# 02_rf_front_end.net
KiCad netlist of a schematic drawn in Altium Designer
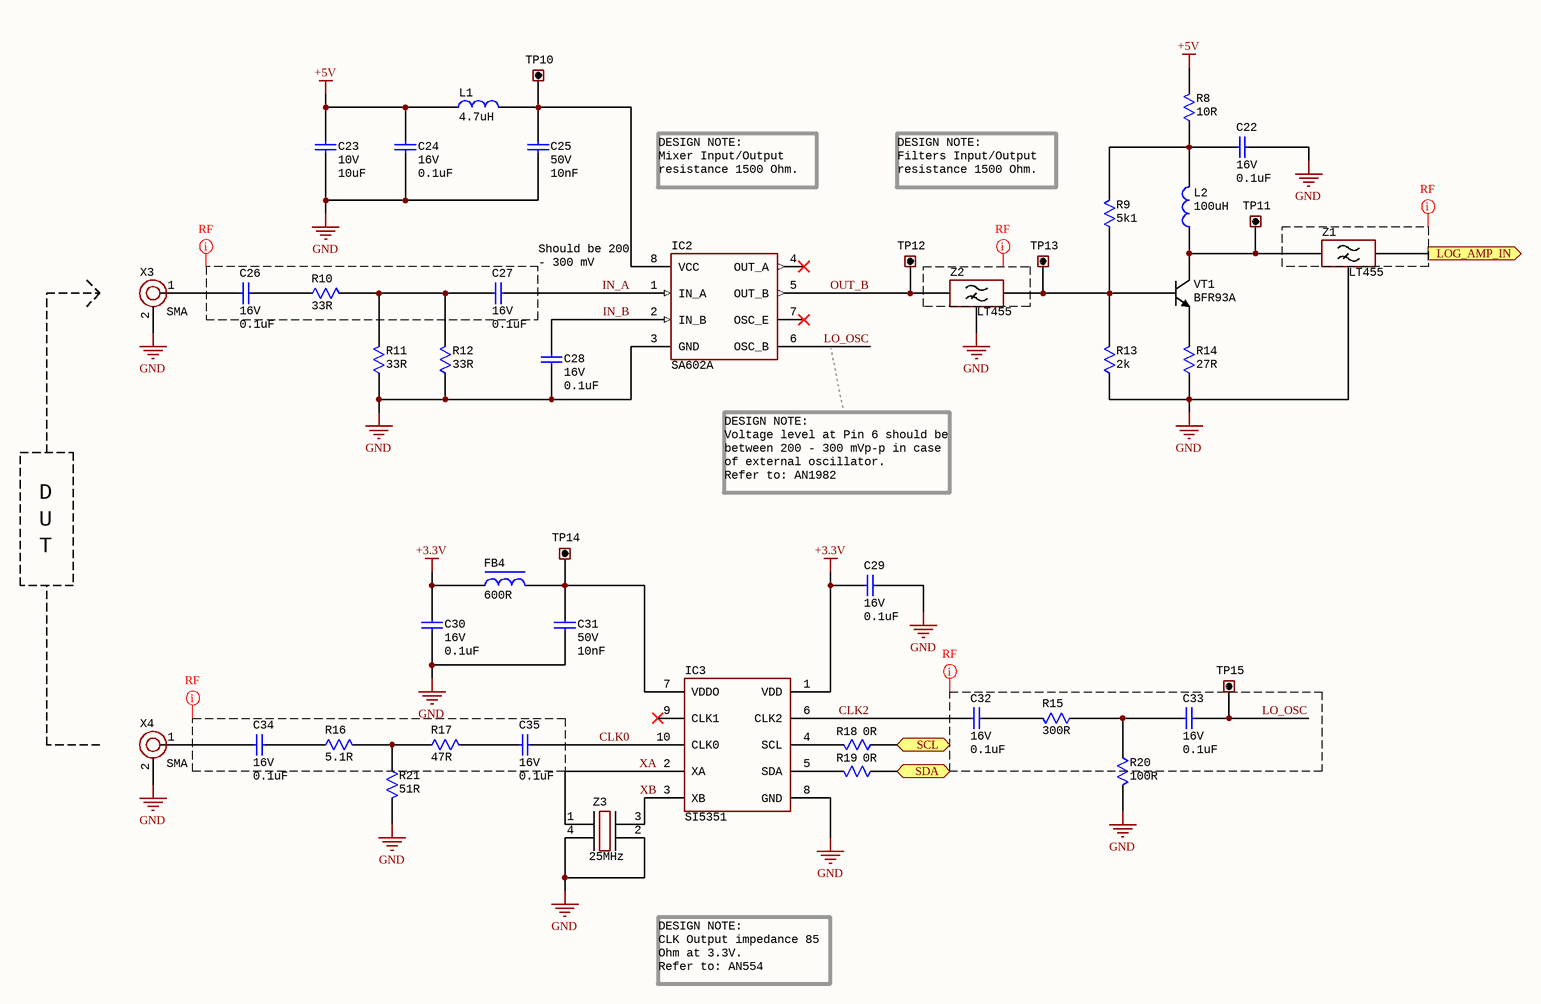
[diagram p0: 02_rf_front_end.SchDoc]

(export (version "E")
  (design (tool "Eeschema 10.0.6"))
  (components
    (comp (ref "C22")
      (value "0.1uF")
      (footprint "standard-case:CAP: 0402")
      (fields
        (field (name "MANUFACTURER") "Samsung Electro-Mechanics")
        (field (name "PARTNUMBER") "CL05B104KO5NNNC")
        (field (name "VALUEMANUFACTURERPARTNUMBER") "Ceramic capacitor, 0.1uF, X7R, ±10%, 16V, 0402, -55...+125°C")
        (field (name "VOLTAGE") "16V")
      )
      (libsource (lib "Schlib") (part "Ceramic"))
    )
    (comp (ref "C23")
      (value "10uF")
      (footprint "standard-case:CAP: 0603")
      (fields
        (field (name "MANUFACTURER") "Samsung Electro-Mechanics")
        (field (name "PARTNUMBER") "CL10A106KP8NNNC")
        (field (name "VALUEMANUFACTURERPARTNUMBER") "Ceramic capacitor, 10uF, X5R, ±10%, 10V, 0603, -55...+125°C")
        (field (name "VOLTAGE") "10V")
      )
      (libsource (lib "Schlib") (part "Ceramic"))
    )
    (comp (ref "C24")
      (value "0.1uF")
      (footprint "standard-case:CAP: 0402")
      (fields
        (field (name "MANUFACTURER") "Samsung Electro-Mechanics")
        (field (name "PARTNUMBER") "CL05B104KO5NNNC")
        (field (name "VALUEMANUFACTURERPARTNUMBER") "Ceramic capacitor, 0.1uF, X7R, ±10%, 16V, 0402, -55...+125°C")
        (field (name "VOLTAGE") "16V")
      )
      (libsource (lib "Schlib") (part "Ceramic"))
    )
    (comp (ref "C25")
      (value "10nF")
      (footprint "standard-case:CAP: 0402")
      (fields
        (field (name "MANUFACTURER") "Samsung Electro-Mechanics")
        (field (name "PARTNUMBER") "CL05B103KB5NNNC")
        (field (name "VALUEMANUFACTURERPARTNUMBER") "Ceramic capacitor, 10nF, X7R, ±10%, 50V, 0402, -55...+125°C")
        (field (name "VOLTAGE") "50V")
      )
      (libsource (lib "Schlib") (part "Ceramic"))
    )
    (comp (ref "C26")
      (value "0.1uF")
      (footprint "standard-case:CAP: 0402")
      (fields
        (field (name "MANUFACTURER") "Samsung Electro-Mechanics")
        (field (name "PARTNUMBER") "CL05B104KO5NNNC")
        (field (name "VALUEMANUFACTURERPARTNUMBER") "Ceramic capacitor, 0.1uF, X7R, ±10%, 16V, 0402, -55...+125°C")
        (field (name "VOLTAGE") "16V")
      )
      (libsource (lib "Schlib") (part "Ceramic"))
    )
    (comp (ref "C27")
      (value "0.1uF")
      (footprint "standard-case:CAP: 0402")
      (fields
        (field (name "MANUFACTURER") "Samsung Electro-Mechanics")
        (field (name "PARTNUMBER") "CL05B104KO5NNNC")
        (field (name "VALUEMANUFACTURERPARTNUMBER") "Ceramic capacitor, 0.1uF, X7R, ±10%, 16V, 0402, -55...+125°C")
        (field (name "VOLTAGE") "16V")
      )
      (libsource (lib "Schlib") (part "Ceramic"))
    )
    (comp (ref "C28")
      (value "0.1uF")
      (footprint "standard-case:CAP: 0402")
      (fields
        (field (name "MANUFACTURER") "Samsung Electro-Mechanics")
        (field (name "PARTNUMBER") "CL05B104KO5NNNC")
        (field (name "VALUEMANUFACTURERPARTNUMBER") "Ceramic capacitor, 0.1uF, X7R, ±10%, 16V, 0402, -55...+125°C")
        (field (name "VOLTAGE") "16V")
      )
      (libsource (lib "Schlib") (part "Ceramic"))
    )
    (comp (ref "C29")
      (value "0.1uF")
      (footprint "standard-case:CAP: 0402")
      (fields
        (field (name "MANUFACTURER") "Samsung Electro-Mechanics")
        (field (name "PARTNUMBER") "CL05B104KO5NNNC")
        (field (name "VALUEMANUFACTURERPARTNUMBER") "Ceramic capacitor, 0.1uF, X7R, ±10%, 16V, 0402, -55...+125°C")
        (field (name "VOLTAGE") "16V")
      )
      (libsource (lib "Schlib") (part "Ceramic"))
    )
    (comp (ref "C30")
      (value "0.1uF")
      (footprint "standard-case:CAP: 0402")
      (fields
        (field (name "MANUFACTURER") "Samsung Electro-Mechanics")
        (field (name "PARTNUMBER") "CL05B104KO5NNNC")
        (field (name "VALUEMANUFACTURERPARTNUMBER") "Ceramic capacitor, 0.1uF, X7R, ±10%, 16V, 0402, -55...+125°C")
        (field (name "VOLTAGE") "16V")
      )
      (libsource (lib "Schlib") (part "Ceramic"))
    )
    (comp (ref "C31")
      (value "10nF")
      (footprint "standard-case:CAP: 0402")
      (fields
        (field (name "MANUFACTURER") "Samsung Electro-Mechanics")
        (field (name "PARTNUMBER") "CL05B103KB5NNNC")
        (field (name "VALUEMANUFACTURERPARTNUMBER") "Ceramic capacitor, 10nF, X7R, ±10%, 50V, 0402, -55...+125°C")
        (field (name "VOLTAGE") "50V")
      )
      (libsource (lib "Schlib") (part "Ceramic"))
    )
    (comp (ref "C32")
      (value "0.1uF")
      (footprint "standard-case:CAP: 0402")
      (fields
        (field (name "MANUFACTURER") "Samsung Electro-Mechanics")
        (field (name "PARTNUMBER") "CL05B104KO5NNNC")
        (field (name "VALUEMANUFACTURERPARTNUMBER") "Ceramic capacitor, 0.1uF, X7R, ±10%, 16V, 0402, -55...+125°C")
        (field (name "VOLTAGE") "16V")
      )
      (libsource (lib "Schlib") (part "Ceramic"))
    )
    (comp (ref "C33")
      (value "0.1uF")
      (footprint "standard-case:CAP: 0402")
      (fields
        (field (name "MANUFACTURER") "Samsung Electro-Mechanics")
        (field (name "PARTNUMBER") "CL05B104KO5NNNC")
        (field (name "VALUEMANUFACTURERPARTNUMBER") "Ceramic capacitor, 0.1uF, X7R, ±10%, 16V, 0402, -55...+125°C")
        (field (name "VOLTAGE") "16V")
      )
      (libsource (lib "Schlib") (part "Ceramic"))
    )
    (comp (ref "C34")
      (value "0.1uF")
      (footprint "standard-case:CAP: 0402")
      (fields
        (field (name "MANUFACTURER") "Samsung Electro-Mechanics")
        (field (name "PARTNUMBER") "CL05B104KO5NNNC")
        (field (name "VALUEMANUFACTURERPARTNUMBER") "Ceramic capacitor, 0.1uF, X7R, ±10%, 16V, 0402, -55...+125°C")
        (field (name "VOLTAGE") "16V")
      )
      (libsource (lib "Schlib") (part "Ceramic"))
    )
    (comp (ref "C35")
      (value "0.1uF")
      (footprint "standard-case:CAP: 0402")
      (fields
        (field (name "MANUFACTURER") "Samsung Electro-Mechanics")
        (field (name "PARTNUMBER") "CL05B104KO5NNNC")
        (field (name "VALUEMANUFACTURERPARTNUMBER") "Ceramic capacitor, 0.1uF, X7R, ±10%, 16V, 0402, -55...+125°C")
        (field (name "VOLTAGE") "16V")
      )
      (libsource (lib "Schlib") (part "Ceramic"))
    )
    (comp (ref "FB4")
      (value "~")
      (footprint "standard-case:IND: 0603")
      (fields
        (field (name "MANUFACTURER") "Sunlord")
        (field (name "PARTNUMBER") "LQP03TNR10J02D")
        (field (name "VALUEMANUFACTURERPARTNUMBER") "Ferrite Bead, , , 0603, 200mA, -55...+125°C")
        (field (name "RESISTANCE") "600R")
      )
      (libsource (lib "Schlib") (part "Ferrite_Bead_SMD"))
    )
    (comp (ref "IC2")
      (value "SA602A")
      (footprint "8-SOIC")
      (description "Integrated Circuit")
      (fields
        (field (name "MANUFACTURER_PART_NUMBER") "SA602AD/01,118")
        (field (name "MOUSER PART NUMBER") "771-SA602AD/01-T")
      )
      (libsource (lib "Schlib") (part "SA602A"))
    )
    (comp (ref "IC3")
      (value "SI5351")
      (footprint "10-MSOP")
      (description "Integrated Circuit")
      (fields
        (field (name "MANUFACTURER_PART_NUMBER") "Si5351A-B-GT")
        (field (name "MOUSER PART NUMBER") "634-SI5351A-B-GT")
      )
      (libsource (lib "Schlib") (part "Si5351A"))
    )
    (comp (ref "L1")
      (value "4.7uH")
      (footprint "standard-case:IND: 0603")
      (fields
        (field (name "MANUFACTURER") "Murata Electronics")
        (field (name "PARTNUMBER") "LQP03TNR10J02D")
        (field (name "VALUEMANUFACTURERPARTNUMBER") "Fixed inductor, 4.7uH, ±5%, 0201, 80mA, -55...+125°C")
      )
      (libsource (lib "Schlib") (part "Inductor_SMD"))
    )
    (comp (ref "L2")
      (value "100uH")
      (footprint "standard-case:IND: 0805")
      (fields
        (field (name "MANUFACTURER") "Murata Electronics")
        (field (name "PARTNUMBER") "LQP03TNR10J02D")
        (field (name "VALUEMANUFACTURERPARTNUMBER") "Fixed inductor, 100uH, ±5%, 0201, 80mA, -55...+125°C")
      )
      (libsource (lib "Schlib") (part "Inductor_SMD"))
    )
    (comp (ref "R8")
      (value "10R")
      (footprint "standard-case:RES: 0603")
      (fields
        (field (name "MANUFACTURER") "Yageo")
        (field (name "PARTNUMBER") "RC0201JR-07100RL")
        (field (name "VALUEMANUFACTURERPARTNUMBER") "Resistor film, 10R, ±5%, 0603, 0.05W, -55...+125°C")
      )
      (libsource (lib "Schlib") (part "Resistor"))
    )
    (comp (ref "R9")
      (value "5k1")
      (footprint "standard-case:RES: 0603")
      (fields
        (field (name "MANUFACTURER") "Yageo")
        (field (name "PARTNUMBER") "RC0201JR-07100RL")
        (field (name "VALUEMANUFACTURERPARTNUMBER") "Resistor film, 5k1, ±5%, 0603, 0.05W, -55...+125°C")
      )
      (libsource (lib "Schlib") (part "Resistor"))
    )
    (comp (ref "R10")
      (value "33R")
      (footprint "standard-case:RES: 0603")
      (fields
        (field (name "MANUFACTURER") "Yageo")
        (field (name "PARTNUMBER") "RC0201JR-07100RL")
        (field (name "VALUEMANUFACTURERPARTNUMBER") "Resistor film, 33R, ±5%, 0603, 0.05W, -55...+125°C")
      )
      (libsource (lib "Schlib") (part "Resistor"))
    )
    (comp (ref "R11")
      (value "33R")
      (footprint "standard-case:RES: 0603")
      (fields
        (field (name "MANUFACTURER") "Yageo")
        (field (name "PARTNUMBER") "RC0201JR-07100RL")
        (field (name "VALUEMANUFACTURERPARTNUMBER") "Resistor film, 33R, ±5%, 0603, 0.05W, -55...+125°C")
      )
      (libsource (lib "Schlib") (part "Resistor"))
    )
    (comp (ref "R12")
      (value "33R")
      (footprint "standard-case:RES: 0603")
      (fields
        (field (name "MANUFACTURER") "Yageo")
        (field (name "PARTNUMBER") "RC0201JR-07100RL")
        (field (name "VALUEMANUFACTURERPARTNUMBER") "Resistor film, 33R, ±5%, 0603, 0.05W, -55...+125°C")
      )
      (libsource (lib "Schlib") (part "Resistor"))
    )
    (comp (ref "R13")
      (value "2k")
      (footprint "standard-case:RES: 0603")
      (fields
        (field (name "MANUFACTURER") "Yageo")
        (field (name "PARTNUMBER") "RC0201JR-07100RL")
        (field (name "VALUEMANUFACTURERPARTNUMBER") "Resistor film, 2k, ±5%, 0603, 0.05W, -55...+125°C")
      )
      (libsource (lib "Schlib") (part "Resistor"))
    )
    (comp (ref "R14")
      (value "27R")
      (footprint "standard-case:RES: 0603")
      (fields
        (field (name "MANUFACTURER") "Yageo")
        (field (name "PARTNUMBER") "RC0201JR-07100RL")
        (field (name "VALUEMANUFACTURERPARTNUMBER") "Resistor film, 27R, ±5%, 0603, 0.05W, -55...+125°C")
      )
      (libsource (lib "Schlib") (part "Resistor"))
    )
    (comp (ref "R15")
      (value "300R")
      (footprint "standard-case:RES: 0603")
      (fields
        (field (name "MANUFACTURER") "Yageo")
        (field (name "PARTNUMBER") "RC0201JR-07100RL")
        (field (name "VALUEMANUFACTURERPARTNUMBER") "Resistor film, 300R, ±5%, 0603, 0.05W, -55...+125°C")
      )
      (libsource (lib "Schlib") (part "Resistor"))
    )
    (comp (ref "R16")
      (value "5.1R")
      (footprint "standard-case:RES: 0603")
      (fields
        (field (name "MANUFACTURER") "Yageo")
        (field (name "PARTNUMBER") "RC0201JR-07100RL")
        (field (name "VALUEMANUFACTURERPARTNUMBER") "Resistor film, 5.1R, ±5%, 0603, 0.05W, -55...+125°C")
      )
      (libsource (lib "Schlib") (part "Resistor"))
    )
    (comp (ref "R17")
      (value "47R")
      (footprint "standard-case:RES: 0603")
      (fields
        (field (name "MANUFACTURER") "Yageo")
        (field (name "PARTNUMBER") "RC0201JR-07100RL")
        (field (name "VALUEMANUFACTURERPARTNUMBER") "Resistor film, 47R, ±5%, 0603, 0.05W, -55...+125°C")
      )
      (libsource (lib "Schlib") (part "Resistor"))
    )
    (comp (ref "R18")
      (value "0R")
      (footprint "standard-case:RES: 0402")
      (fields
        (field (name "MANUFACTURER") "Yageo")
        (field (name "PARTNUMBER") "RC0201JR-07100RL")
        (field (name "VALUEMANUFACTURERPARTNUMBER") "Resistor film, 0R, ±5%, 0603, 0.05W, -55...+125°C")
      )
      (libsource (lib "Schlib") (part "Resistor"))
    )
    (comp (ref "R19")
      (value "0R")
      (footprint "standard-case:RES: 0402")
      (fields
        (field (name "MANUFACTURER") "Yageo")
        (field (name "PARTNUMBER") "RC0201JR-07100RL")
        (field (name "VALUEMANUFACTURERPARTNUMBER") "Resistor film, 0R, ±5%, 0603, 0.05W, -55...+125°C")
      )
      (libsource (lib "Schlib") (part "Resistor"))
    )
    (comp (ref "R20")
      (value "100R")
      (footprint "standard-case:RES: 0603")
      (fields
        (field (name "MANUFACTURER") "Yageo")
        (field (name "PARTNUMBER") "RC0201JR-07100RL")
        (field (name "VALUEMANUFACTURERPARTNUMBER") "Resistor film, 100R, ±5%, 0603, 0.05W, -55...+125°C")
      )
      (libsource (lib "Schlib") (part "Resistor"))
    )
    (comp (ref "R21")
      (value "51R")
      (footprint "standard-case:RES: 0603")
      (fields
        (field (name "MANUFACTURER") "Yageo")
        (field (name "PARTNUMBER") "RC0201JR-07100RL")
        (field (name "VALUEMANUFACTURERPARTNUMBER") "Resistor film, 51R, ±5%, 0603, 0.05W, -55...+125°C")
      )
      (libsource (lib "Schlib") (part "Resistor"))
    )
    (comp (ref "TP10")
      (value "~")
      (footprint "CON: test_point")
      (fields
        (field (name "MANUFACTURER") "Keystone")
        (field (name "VALUEMANUFACTURERPARTNUMBER") "Test point, Keystone, 5001")
        (field (name "PARTNUMBER") "5001")
      )
      (libsource (lib "Schlib") (part "Connector_Test_Point"))
    )
    (comp (ref "TP11")
      (value "~")
      (footprint "CON: test_point")
      (fields
        (field (name "MANUFACTURER") "Keystone")
        (field (name "VALUEMANUFACTURERPARTNUMBER") "Test point, Keystone, 5001")
        (field (name "PARTNUMBER") "5001")
      )
      (libsource (lib "Schlib") (part "Connector_Test_Point"))
    )
    (comp (ref "TP12")
      (value "~")
      (footprint "CON: test_point")
      (fields
        (field (name "MANUFACTURER") "Keystone")
        (field (name "VALUEMANUFACTURERPARTNUMBER") "Test point, Keystone, 5001")
        (field (name "PARTNUMBER") "5001")
      )
      (libsource (lib "Schlib") (part "Connector_Test_Point"))
    )
    (comp (ref "TP13")
      (value "~")
      (footprint "CON: test_point")
      (fields
        (field (name "MANUFACTURER") "Keystone")
        (field (name "VALUEMANUFACTURERPARTNUMBER") "Test point, Keystone, 5001")
        (field (name "PARTNUMBER") "5001")
      )
      (libsource (lib "Schlib") (part "Connector_Test_Point"))
    )
    (comp (ref "TP14")
      (value "~")
      (footprint "CON: test_point")
      (fields
        (field (name "MANUFACTURER") "Keystone")
        (field (name "VALUEMANUFACTURERPARTNUMBER") "Test point, Keystone, 5001")
        (field (name "PARTNUMBER") "5001")
      )
      (libsource (lib "Schlib") (part "Connector_Test_Point"))
    )
    (comp (ref "TP15")
      (value "~")
      (footprint "CON: test_point")
      (fields
        (field (name "MANUFACTURER") "Keystone")
        (field (name "VALUEMANUFACTURERPARTNUMBER") "Test point, Keystone, 5001")
        (field (name "PARTNUMBER") "5001")
      )
      (libsource (lib "") (part "Connector_Test_Point_1"))
    )
    (comp (ref "VT1")
      (value "~")
      (footprint "standard-case:SOT23")
      (fields
        (field (name "MANUFACTURER") "ON Semiconductor")
        (field (name "VALUEMANUFACTURERPARTNUMBER") "NPN transistor, 45V, 100mA, 100MHz, 300mW, 0.6V, 420, SOT-23, -55...+125°C")
        (field (name "PARTNUMBER") "BFR93A")
      )
      (libsource (lib "Schlib") (part "BJT_NPN_132"))
    )
    (comp (ref "X3")
      (value "~")
      (footprint "CON: SMA EDGE MOUNT")
      (fields
        (field (name "MANUFACTURER") "TE Connectivity")
        (field (name "VALUEMANUFACTURERPARTNUMBER") "Connector SMA, 50 Ohm, 3GHz")
        (field (name "PARTNUMBER") "5-1814832-1")
        (field (name "COMMENTTEXT") "SMA")
      )
      (libsource (lib "Schlib") (part "Connector_SMA"))
    )
    (comp (ref "X4")
      (value "~")
      (footprint "CON: SMA EDGE MOUNT")
      (fields
        (field (name "MANUFACTURER") "TE Connectivity")
        (field (name "VALUEMANUFACTURERPARTNUMBER") "Connector SMA, 50 Ohm, 3GHz")
        (field (name "PARTNUMBER") "5-1814832-1")
        (field (name "COMMENTTEXT") "SMA")
      )
      (libsource (lib "Schlib") (part "Connector_SMA"))
    )
    (comp (ref "Z1")
      (value "~")
      (footprint "CFUKG455")
      (fields (field (name "PARTNUMBER") "LT455"))
      (libsource (lib "Schlib") (part "LT455"))
    )
    (comp (ref "Z2")
      (value "~")
      (footprint "CFUKG455")
      (fields (field (name "PARTNUMBER") "LT455"))
      (libsource (lib "Schlib") (part "LT455"))
    )
    (comp (ref "Z3")
      (value "~")
      (footprint "custom-case:OSC: 3225")
      (fields
        (field (name "MANUFACTURER") "Yangxing Tech")
        (field (name "PARTNUMBER") "X322525MOB4SI")
        (field (name "VALUEMANUFACTURERPARTNUMBER") "Oscilator, 25MHz, HCMOS, ±50ppm, case 3225, -20...+70°C")
        (field (name "FREQUENCY") "25MHz")
      )
      (libsource (lib "Schlib") (part "Oscilator"))
    )
  )
  (nets
    (net (code "1") (name "+3.3V") (class "Default")
      (node (ref "C29") (pin "1") (pinfunction "1_1") (pintype "passive"))
      (node (ref "C30") (pin "1") (pinfunction "1_1") (pintype "passive"))
      (node (ref "FB4") (pin "2") (pinfunction "2_2") (pintype "passive"))
      (node (ref "IC3") (pin "1") (pinfunction "VDD_1") (pintype "passive"))
    )
    (net (code "2") (name "+5V") (class "Default")
      (node (ref "C23") (pin "1") (pinfunction "1_1") (pintype "passive"))
      (node (ref "C24") (pin "1") (pinfunction "1_1") (pintype "passive"))
      (node (ref "L1") (pin "2") (pinfunction "2_2") (pintype "passive"))
      (node (ref "R8") (pin "2") (pinfunction "2_2") (pintype "passive"))
    )
    (net (code "3") (name "/CLK0") (class "Default")
      (node (ref "C35") (pin "1") (pinfunction "1_1") (pintype "passive"))
      (node (ref "IC3") (pin "10") (pinfunction "CLK0_10") (pintype "passive"))
    )
    (net (code "4") (name "/CLK2") (class "Default")
      (node (ref "C32") (pin "2") (pinfunction "2_2") (pintype "passive"))
      (node (ref "IC3") (pin "6") (pinfunction "CLK2_6") (pintype "passive"))
    )
    (net (code "5") (name "/IN_A") (class "Default")
      (node (ref "C27") (pin "2") (pinfunction "2_2") (pintype "passive"))
      (node (ref "IC2") (pin "1") (pinfunction "IN_A_1") (pintype "input"))
    )
    (net (code "6") (name "/IN_B") (class "Default")
      (node (ref "C28") (pin "2") (pinfunction "2_2") (pintype "passive"))
      (node (ref "IC2") (pin "2") (pinfunction "IN_B_2") (pintype "input"))
    )
    (net (code "7") (name "/LOG_AMP_IN") (class "Default")
      (node (ref "Z1") (pin "2") (pinfunction "OUT_2") (pintype "passive"))
    )
    (net (code "8") (name "/LO_OSC") (class "Default")
      (node (ref "C33") (pin "1") (pinfunction "1_1") (pintype "passive"))
      (node (ref "IC2") (pin "6") (pinfunction "OSC_B_6") (pintype "passive"))
      (node (ref "TP15") (pin "1") (pinfunction "1_1") (pintype "passive"))
    )
    (net (code "9") (name "/OUT_B") (class "Default")
      (node (ref "IC2") (pin "5") (pinfunction "OUT_B_5") (pintype "output"))
      (node (ref "TP12") (pin "1") (pinfunction "1_1") (pintype "passive"))
      (node (ref "Z2") (pin "1") (pinfunction "IN_1") (pintype "passive"))
    )
    (net (code "10") (name "/SCL") (class "Default")
      (node (ref "R18") (pin "1") (pinfunction "1_1") (pintype "passive"))
    )
    (net (code "11") (name "/SDA") (class "Default")
      (node (ref "R19") (pin "1") (pinfunction "1_1") (pintype "passive"))
    )
    (net (code "12") (name "/XA") (class "Default")
      (node (ref "IC3") (pin "2") (pinfunction "XA_2") (pintype "passive"))
      (node (ref "Z3") (pin "1") (pinfunction "1_1") (pintype "passive"))
    )
    (net (code "13") (name "/XB") (class "Default")
      (node (ref "IC3") (pin "3") (pinfunction "XB_3") (pintype "passive"))
      (node (ref "Z3") (pin "3") (pinfunction "3_3") (pintype "passive"))
    )
    (net (code "14") (name "GND") (class "Default")
      (node (ref "C22") (pin "2") (pinfunction "2_2") (pintype "passive"))
      (node (ref "C23") (pin "2") (pinfunction "2_2") (pintype "passive"))
      (node (ref "C24") (pin "2") (pinfunction "2_2") (pintype "passive"))
      (node (ref "C25") (pin "2") (pinfunction "2_2") (pintype "passive"))
      (node (ref "C28") (pin "1") (pinfunction "1_1") (pintype "passive"))
      (node (ref "C29") (pin "2") (pinfunction "2_2") (pintype "passive"))
      (node (ref "C30") (pin "2") (pinfunction "2_2") (pintype "passive"))
      (node (ref "C31") (pin "2") (pinfunction "2_2") (pintype "passive"))
      (node (ref "IC2") (pin "3") (pinfunction "GND_3") (pintype "power_in"))
      (node (ref "IC3") (pin "8") (pinfunction "GND_8") (pintype "passive"))
      (node (ref "R11") (pin "1") (pinfunction "1_1") (pintype "passive"))
      (node (ref "R12") (pin "1") (pinfunction "1_1") (pintype "passive"))
      (node (ref "R13") (pin "1") (pinfunction "1_1") (pintype "passive"))
      (node (ref "R14") (pin "1") (pinfunction "1_1") (pintype "passive"))
      (node (ref "R20") (pin "1") (pinfunction "1_1") (pintype "passive"))
      (node (ref "R21") (pin "1") (pinfunction "1_1") (pintype "passive"))
      (node (ref "X3") (pin "2") (pinfunction "2_2") (pintype "passive"))
      (node (ref "X4") (pin "2") (pinfunction "2_2") (pintype "passive"))
      (node (ref "Z1") (pin "3") (pinfunction "GND_3") (pintype "passive"))
      (node (ref "Z2") (pin "3") (pinfunction "GND_3") (pintype "passive"))
      (node (ref "Z3") (pin "2") (pinfunction "2_2") (pintype "passive"))
      (node (ref "Z3") (pin "4") (pinfunction "4_4") (pintype "passive"))
    )
    (net (code "15") (name "Net-(C22-Pad1)") (class "Default")
      (node (ref "C22") (pin "1") (pinfunction "1_1") (pintype "passive"))
      (node (ref "L2") (pin "1") (pinfunction "1_1") (pintype "passive"))
      (node (ref "R8") (pin "1") (pinfunction "1_1") (pintype "passive"))
      (node (ref "R9") (pin "2") (pinfunction "2_2") (pintype "passive"))
    )
    (net (code "16") (name "Net-(C26-Pad1)") (class "Default")
      (node (ref "C26") (pin "1") (pinfunction "1_1") (pintype "passive"))
      (node (ref "X3") (pin "1") (pinfunction "1_1") (pintype "passive"))
    )
    (net (code "17") (name "Net-(C26-Pad2)") (class "Default")
      (node (ref "C26") (pin "2") (pinfunction "2_2") (pintype "passive"))
      (node (ref "R10") (pin "1") (pinfunction "1_1") (pintype "passive"))
    )
    (net (code "18") (name "Net-(C27-Pad1)") (class "Default")
      (node (ref "C27") (pin "1") (pinfunction "1_1") (pintype "passive"))
      (node (ref "R10") (pin "2") (pinfunction "2_2") (pintype "passive"))
      (node (ref "R11") (pin "2") (pinfunction "2_2") (pintype "passive"))
      (node (ref "R12") (pin "2") (pinfunction "2_2") (pintype "passive"))
    )
    (net (code "19") (name "Net-(C32-Pad1)") (class "Default")
      (node (ref "C32") (pin "1") (pinfunction "1_1") (pintype "passive"))
      (node (ref "R15") (pin "1") (pinfunction "1_1") (pintype "passive"))
    )
    (net (code "20") (name "Net-(C33-Pad2)") (class "Default")
      (node (ref "C33") (pin "2") (pinfunction "2_2") (pintype "passive"))
      (node (ref "R15") (pin "2") (pinfunction "2_2") (pintype "passive"))
      (node (ref "R20") (pin "2") (pinfunction "2_2") (pintype "passive"))
    )
    (net (code "21") (name "Net-(C34-Pad1)") (class "Default")
      (node (ref "C34") (pin "1") (pinfunction "1_1") (pintype "passive"))
      (node (ref "R16") (pin "2") (pinfunction "2_2") (pintype "passive"))
    )
    (net (code "22") (name "Net-(C34-Pad2)") (class "Default")
      (node (ref "C34") (pin "2") (pinfunction "2_2") (pintype "passive"))
      (node (ref "X4") (pin "1") (pinfunction "1_1") (pintype "passive"))
    )
    (net (code "23") (name "Net-(C35-Pad2)") (class "Default")
      (node (ref "C35") (pin "2") (pinfunction "2_2") (pintype "passive"))
      (node (ref "R17") (pin "1") (pinfunction "1_1") (pintype "passive"))
    )
    (net (code "24") (name "Net-(IC2-VCC)") (class "Default")
      (node (ref "C25") (pin "1") (pinfunction "1_1") (pintype "passive"))
      (node (ref "IC2") (pin "8") (pinfunction "VCC_8") (pintype "power_in"))
      (node (ref "L1") (pin "1") (pinfunction "1_1") (pintype "passive"))
      (node (ref "TP10") (pin "1") (pinfunction "1_1") (pintype "passive"))
    )
    (net (code "25") (name "Net-(IC3-SCL)") (class "Default")
      (node (ref "IC3") (pin "4") (pinfunction "SCL_4") (pintype "passive"))
      (node (ref "R18") (pin "2") (pinfunction "2_2") (pintype "passive"))
    )
    (net (code "26") (name "Net-(IC3-SDA)") (class "Default")
      (node (ref "IC3") (pin "5") (pinfunction "SDA_5") (pintype "passive"))
      (node (ref "R19") (pin "2") (pinfunction "2_2") (pintype "passive"))
    )
    (net (code "27") (name "Net-(IC3-VDDO)") (class "Default")
      (node (ref "C31") (pin "1") (pinfunction "1_1") (pintype "passive"))
      (node (ref "FB4") (pin "1") (pinfunction "1_1") (pintype "passive"))
      (node (ref "IC3") (pin "7") (pinfunction "VDDO_7") (pintype "passive"))
      (node (ref "TP14") (pin "1") (pinfunction "1_1") (pintype "passive"))
    )
    (net (code "28") (name "Net-(R16-Pad1)") (class "Default")
      (node (ref "R16") (pin "1") (pinfunction "1_1") (pintype "passive"))
      (node (ref "R17") (pin "2") (pinfunction "2_2") (pintype "passive"))
      (node (ref "R21") (pin "2") (pinfunction "2_2") (pintype "passive"))
    )
    (net (code "29") (name "Net-(VT1-B)") (class "Default")
      (node (ref "R13") (pin "2") (pinfunction "2_2") (pintype "passive"))
      (node (ref "R9") (pin "1") (pinfunction "1_1") (pintype "passive"))
      (node (ref "TP13") (pin "1") (pinfunction "1_1") (pintype "passive"))
      (node (ref "VT1") (pin "1") (pinfunction "B_1") (pintype "passive"))
      (node (ref "Z2") (pin "2") (pinfunction "OUT_2") (pintype "passive"))
    )
    (net (code "30") (name "Net-(VT1-C)") (class "Default")
      (node (ref "L2") (pin "2") (pinfunction "2_2") (pintype "passive"))
      (node (ref "TP11") (pin "1") (pinfunction "1_1") (pintype "passive"))
      (node (ref "VT1") (pin "3") (pinfunction "C_3") (pintype "passive"))
      (node (ref "Z1") (pin "1") (pinfunction "IN_1") (pintype "passive"))
    )
    (net (code "31") (name "Net-(VT1-E)") (class "Default")
      (node (ref "R14") (pin "2") (pinfunction "2_2") (pintype "passive"))
      (node (ref "VT1") (pin "2") (pinfunction "E_2") (pintype "passive"))
    )
    (net (code "32") (name "unconnected-(IC2-OSC_E-Pad7)") (class "Default")
      (node (ref "IC2") (pin "7") (pinfunction "OSC_E_7") (pintype "passive+no_connect"))
    )
    (net (code "33") (name "unconnected-(IC2-OUT_A-Pad4)") (class "Default")
      (node (ref "IC2") (pin "4") (pinfunction "OUT_A_4") (pintype "output+no_connect"))
    )
    (net (code "34") (name "unconnected-(IC3-CLK1-Pad9)") (class "Default")
      (node (ref "IC3") (pin "9") (pinfunction "CLK1_9") (pintype "passive+no_connect"))
    )
  )
)
